# CW308T_STM32FSOCKET_Micro.net
KiCad netlist of a schematic drawn in Altium Designer
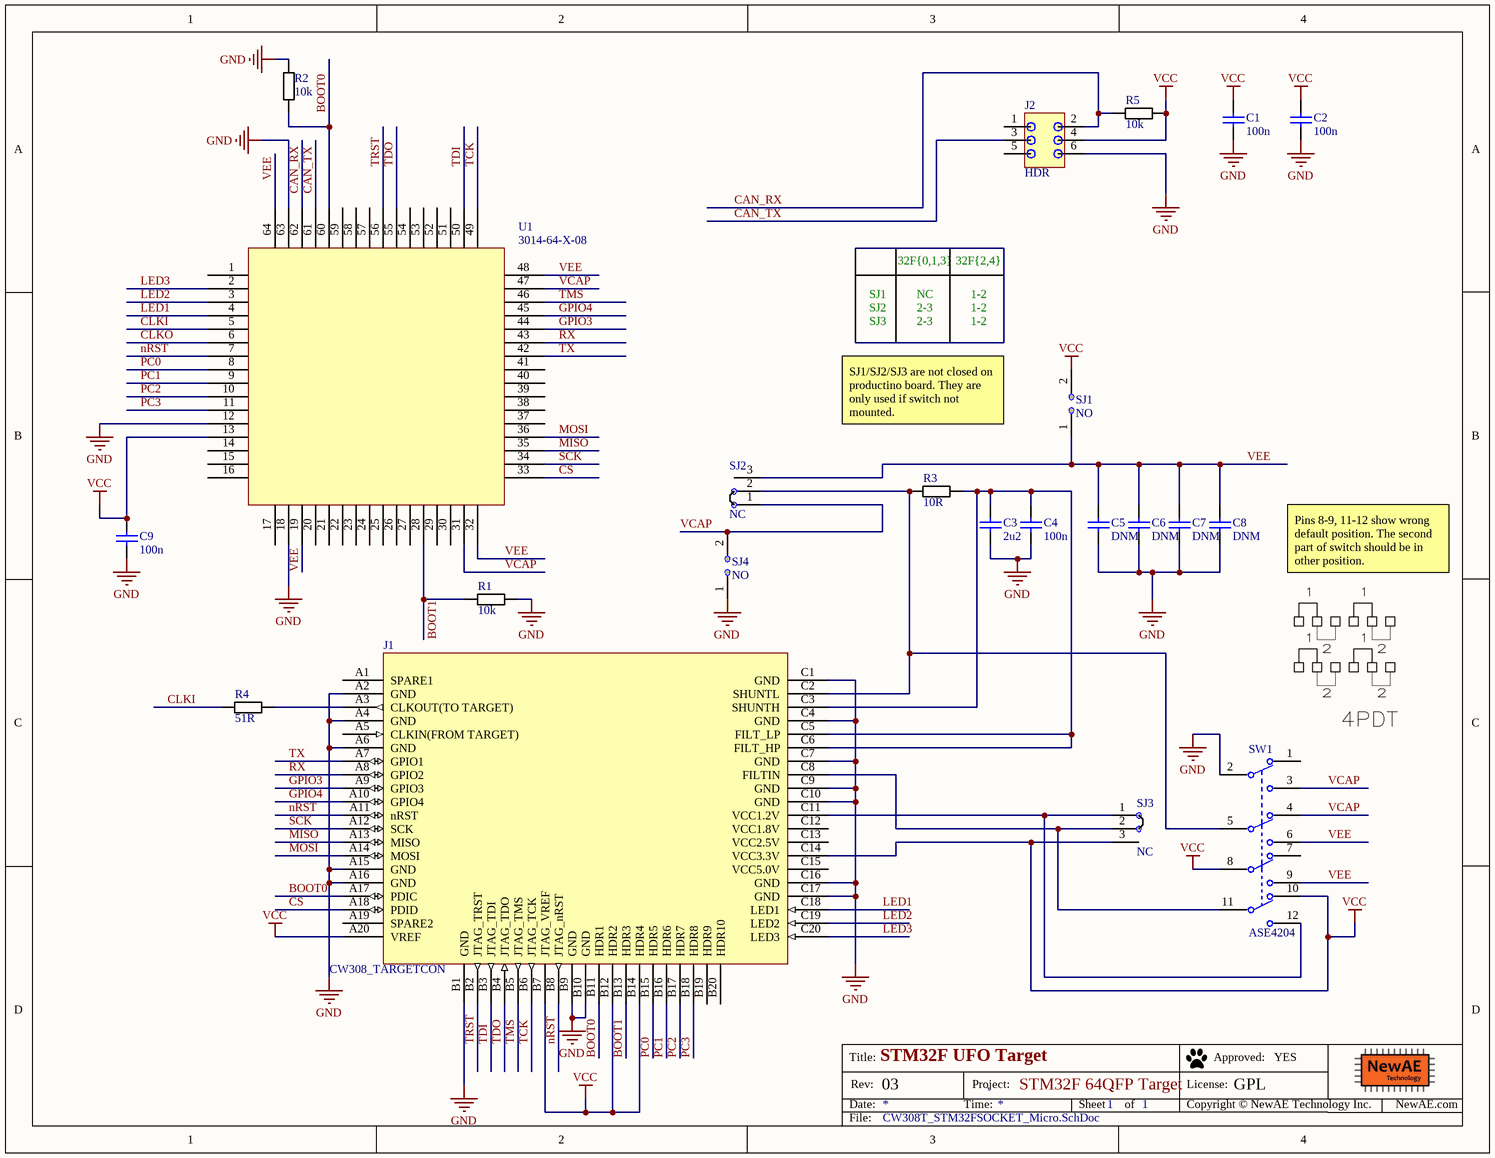
[diagram p0: CW308T_STM32FSOCKET_Micro.SchDoc]

(export (version "E")
  (design (tool "Eeschema 10.0.6"))
  (components
    (comp (ref "C1")
      (value "100n")
      (footprint "CAPC0603_M")
      (description "100n, 0603")
      (fields (field (name "PART NUMBER") "CCHIP-100n-0603"))
      (libsource (lib "NewAE_AltiumLib") (part "CAP"))
    )
    (comp (ref "C2")
      (value "100n")
      (footprint "CAPC0603_M")
      (description "100n, 0603")
      (fields (field (name "PART NUMBER") "CCHIP-100n-0603"))
      (libsource (lib "NewAE_AltiumLib") (part "CAP"))
    )
    (comp (ref "C3")
      (value "2u2")
      (footprint "CAPC0603_M")
      (description "2u2, 0603")
      (fields (field (name "PART NUMBER") "CCHIP-2u2-0603"))
      (libsource (lib "NewAE_AltiumLib") (part "CAP"))
    )
    (comp (ref "C4")
      (value "100n")
      (footprint "CAPC0603_M")
      (description "100n, 0603")
      (fields (field (name "PART NUMBER") "CCHIP-100n-0603"))
      (libsource (lib "NewAE_AltiumLib") (part "CAP"))
    )
    (comp (ref "C5")
      (value "DNM")
      (footprint "CAPC0603_M")
      (description "DNM, 0603")
      (fields (field (name "PART NUMBER") "CCHIP-DNM-0603"))
      (libsource (lib "NewAE_AltiumLib") (part "CAP"))
    )
    (comp (ref "C6")
      (value "DNM")
      (footprint "CAPC0603_M")
      (description "DNM, 0603")
      (fields (field (name "PART NUMBER") "CCHIP-DNM-0603"))
      (libsource (lib "NewAE_AltiumLib") (part "CAP"))
    )
    (comp (ref "C7")
      (value "DNM")
      (footprint "CAPC0603_M")
      (description "DNM, 0603")
      (fields (field (name "PART NUMBER") "CCHIP-DNM-0603"))
      (libsource (lib "NewAE_AltiumLib") (part "CAP"))
    )
    (comp (ref "C8")
      (value "DNM")
      (footprint "CAPC0603_M")
      (description "DNM, 0603")
      (fields (field (name "PART NUMBER") "CCHIP-DNM-0603"))
      (libsource (lib "NewAE_AltiumLib") (part "CAP"))
    )
    (comp (ref "C9")
      (value "100n")
      (footprint "CAPC0603_M")
      (description "100n, 0603")
      (fields (field (name "PART NUMBER") "CCHIP-100n-0603"))
      (libsource (lib "NewAE_AltiumLib") (part "CAP"))
    )
    (comp (ref "J1")
      (value "CW308_TARGETCON")
      (footprint "CW308_TBOARD_CONN")
      (description "CW308 \"Standard\" Target Board Connector")
      (fields (field (name "PART NUMBER") "CW308_TBOARD"))
      (libsource (lib "NewAE_AltiumLib") (part "CW308_TBOARD"))
    )
    (comp (ref "J2")
      (value "HDR")
      (footprint "HDR_6PIN_2ROW_SHROUD")
      (description "HDR, Male, 6-Pin, 2 Row, Shrouded")
      (fields (field (name "PART NUMBER") "HDR_6PIN_2ROW_SHROUD"))
      (libsource (lib "NewAE_AltiumLib") (part "CON6_2ROW"))
    )
    (comp (ref "R1")
      (value "10k")
      (footprint "RESC1608X55N")
      (description "10k res, 0603, 1%, 1/10W")
      (fields (field (name "PART NUMBER") "RCHIP-10K-0603") (field (name "TOLERANCE") "1%"))
      (libsource (lib "NewAE_AltiumLib") (part "RES-EU"))
    )
    (comp (ref "R2")
      (value "10k")
      (footprint "RESC1608X55N")
      (description "10k res, 0603, 1%, 1/10W")
      (fields (field (name "PART NUMBER") "RCHIP-10K-0603") (field (name "TOLERANCE") "1%"))
      (libsource (lib "") (part "RES-EU_1"))
    )
    (comp (ref "R3")
      (value "10R")
      (footprint "RESC1608X55N")
      (description "10R res, 0603, 1%, 1/10W")
      (fields (field (name "PART NUMBER") "RCHIP-10R-0603") (field (name "TOLERANCE") "1%"))
      (libsource (lib "NewAE_AltiumLib") (part "RES-EU"))
    )
    (comp (ref "R4")
      (value "51R")
      (footprint "RESC1608X55N")
      (description "100R res, 0603, 1%, 1/10W")
      (fields (field (name "PART NUMBER") "RCHIP-100R-0603") (field (name "TOLERANCE") "1%"))
      (libsource (lib "NewAE_AltiumLib") (part "RES-EU"))
    )
    (comp (ref "R5")
      (value "10k")
      (footprint "RESC1608X55N")
      (description "10k res, 0603, 1%, 1/10W")
      (fields (field (name "PART NUMBER") "RCHIP-10K-0603") (field (name "TOLERANCE") "1%"))
      (libsource (lib "NewAE_AltiumLib") (part "RES-EU"))
    )
    (comp (ref "SJ1")
      (value "NO")
      (footprint "SJ_2S_NO")
      (description "Solder Jumper, NO")
      (fields (field (name "PART NUMBER") "SJ_2S_NO"))
      (libsource (lib "NewAE_AltiumLib") (part "SJ_2S_NO"))
    )
    (comp (ref "SJ2")
      (value "NC")
      (footprint "SJ_3S_NC12")
      (description "Solder Jumper, NC")
      (fields (field (name "PART NUMBER") "SJ_3S_12JMP"))
      (libsource (lib "NewAE_AltiumLib") (part "SJ_3S_12JMP"))
    )
    (comp (ref "SJ3")
      (value "NC")
      (footprint "SJ_3S_NC12")
      (description "Solder Jumper, NC")
      (fields (field (name "PART NUMBER") "SJ_3S_12JMP"))
      (libsource (lib "NewAE_AltiumLib") (part "SJ_3S_12JMP"))
    )
    (comp (ref "SJ4")
      (value "NO")
      (footprint "SJ_2S_NO")
      (description "Solder Jumper, NO")
      (fields (field (name "PART NUMBER") "SJ_2S_NO"))
      (libsource (lib "NewAE_AltiumLib") (part "SJ_2S_NO"))
    )
    (comp (ref "SW1")
      (value "ASE4204")
      (footprint "FP-ASE4204-MFG")
      (description "Pushbutton Switch SPST-NO Keyswitch, Illuminated Through Hole")
      (libsource (lib "Altium Content Vault") (part "ed2fb4c80255b159646d1d6e4c6c74d"))
    )
    (comp (ref "U1")
      (value "3014-64-X-08")
      (footprint "3014-64-X-08")
      (libsource (lib "tqfp64socket") (part "TQFP64_SOCKET"))
    )
  )
  (nets
    (net (code "1") (name "/BOOT0") (class "Default")
      (node (ref "J1") (pin "A17") (pinfunction "PDIC_A17") (pintype "bidirectional"))
      (node (ref "J1") (pin "B11") (pinfunction "HDR1_B11") (pintype "passive"))
      (node (ref "R2") (pin "1") (pinfunction "1_1") (pintype "passive"))
      (node (ref "U1") (pin "60") (pintype "passive"))
    )
    (net (code "2") (name "/BOOT1") (class "Default")
      (node (ref "J1") (pin "B13") (pinfunction "HDR3_B13") (pintype "passive"))
      (node (ref "R1") (pin "1") (pinfunction "1_1") (pintype "passive"))
      (node (ref "U1") (pin "28") (pintype "passive"))
    )
    (net (code "3") (name "/CAN_RX") (class "Default")
      (node (ref "J2") (pin "2") (pinfunction "2_2") (pintype "passive"))
      (node (ref "R5") (pin "1") (pinfunction "1_1") (pintype "passive"))
      (node (ref "U1") (pin "62") (pintype "passive"))
    )
    (net (code "4") (name "/CAN_TX") (class "Default")
      (node (ref "J2") (pin "3") (pinfunction "3_3") (pintype "passive"))
      (node (ref "U1") (pin "61") (pintype "passive"))
    )
    (net (code "5") (name "/CLKI") (class "Default")
      (node (ref "R4") (pin "1") (pinfunction "1_1") (pintype "passive"))
      (node (ref "U1") (pin "5") (pintype "passive"))
    )
    (net (code "6") (name "/CLKO") (class "Default") (node (ref "U1") (pin "6") (pintype "passive")))
    (net (code "7") (name "/CS") (class "Default")
      (node (ref "J1") (pin "A18") (pinfunction "PDID_A18") (pintype "bidirectional"))
      (node (ref "U1") (pin "33") (pintype "passive"))
    )
    (net (code "8") (name "/GPIO3") (class "Default")
      (node (ref "J1") (pin "A9") (pinfunction "GPIO3_A9") (pintype "bidirectional"))
      (node (ref "U1") (pin "44") (pintype "passive"))
    )
    (net (code "9") (name "/GPIO4") (class "Default")
      (node (ref "J1") (pin "A10") (pinfunction "GPIO4_A10") (pintype "bidirectional"))
      (node (ref "U1") (pin "45") (pintype "passive"))
    )
    (net (code "10") (name "/LED1") (class "Default")
      (node (ref "J1") (pin "C18") (pinfunction "LED1_C18") (pintype "input"))
      (node (ref "U1") (pin "4") (pintype "passive"))
    )
    (net (code "11") (name "/LED2") (class "Default")
      (node (ref "J1") (pin "C19") (pinfunction "LED2_C19") (pintype "input"))
      (node (ref "U1") (pin "3") (pintype "passive"))
    )
    (net (code "12") (name "/LED3") (class "Default")
      (node (ref "J1") (pin "C20") (pinfunction "LED3_C20") (pintype "input"))
      (node (ref "U1") (pin "2") (pintype "passive"))
    )
    (net (code "13") (name "/MISO") (class "Default")
      (node (ref "J1") (pin "A13") (pinfunction "MISO_A13") (pintype "bidirectional"))
      (node (ref "U1") (pin "35") (pintype "passive"))
    )
    (net (code "14") (name "/MOSI") (class "Default")
      (node (ref "J1") (pin "A14") (pinfunction "MOSI_A14") (pintype "bidirectional"))
      (node (ref "U1") (pin "36") (pintype "passive"))
    )
    (net (code "15") (name "/PC0") (class "Default")
      (node (ref "J1") (pin "B15") (pinfunction "HDR5_B15") (pintype "passive"))
      (node (ref "U1") (pin "8") (pintype "passive"))
    )
    (net (code "16") (name "/PC1") (class "Default")
      (node (ref "J1") (pin "B16") (pinfunction "HDR6_B16") (pintype "passive"))
      (node (ref "U1") (pin "9") (pintype "passive"))
    )
    (net (code "17") (name "/PC2") (class "Default")
      (node (ref "J1") (pin "B17") (pinfunction "HDR7_B17") (pintype "passive"))
      (node (ref "U1") (pin "10") (pintype "passive"))
    )
    (net (code "18") (name "/PC3") (class "Default")
      (node (ref "J1") (pin "B18") (pinfunction "HDR8_B18") (pintype "passive"))
      (node (ref "U1") (pin "11") (pintype "passive"))
    )
    (net (code "19") (name "/RX") (class "Default")
      (node (ref "J1") (pin "A8") (pinfunction "GPIO2_A8") (pintype "bidirectional"))
      (node (ref "U1") (pin "43") (pintype "passive"))
    )
    (net (code "20") (name "/SCK") (class "Default")
      (node (ref "J1") (pin "A12") (pinfunction "SCK_A12") (pintype "bidirectional"))
      (node (ref "U1") (pin "34") (pintype "passive"))
    )
    (net (code "21") (name "/TCK") (class "Default")
      (node (ref "J1") (pin "B6") (pinfunction "JTAG_TCK_B6") (pintype "output"))
      (node (ref "U1") (pin "49") (pintype "passive"))
    )
    (net (code "22") (name "/TDI") (class "Default")
      (node (ref "J1") (pin "B3") (pinfunction "JTAG_TDI_B3") (pintype "output"))
      (node (ref "U1") (pin "50") (pintype "passive"))
    )
    (net (code "23") (name "/TDO") (class "Default")
      (node (ref "J1") (pin "B4") (pinfunction "JTAG_TDO_B4") (pintype "input"))
      (node (ref "U1") (pin "55") (pintype "passive"))
    )
    (net (code "24") (name "/TMS") (class "Default")
      (node (ref "J1") (pin "B5") (pinfunction "JTAG_TMS_B5") (pintype "output"))
      (node (ref "U1") (pin "46") (pintype "passive"))
    )
    (net (code "25") (name "/TRST") (class "Default")
      (node (ref "J1") (pin "B2") (pinfunction "JTAG_TRST_B2") (pintype "output"))
      (node (ref "U1") (pin "56") (pintype "passive"))
    )
    (net (code "26") (name "/TX") (class "Default")
      (node (ref "J1") (pin "A7") (pinfunction "GPIO1_A7") (pintype "bidirectional"))
      (node (ref "U1") (pin "42") (pintype "passive"))
    )
    (net (code "27") (name "/VCAP") (class "Default")
      (node (ref "SJ2") (pin "1") (pinfunction "1_1") (pintype "passive"))
      (node (ref "SJ4") (pin "2") (pinfunction "2_2") (pintype "passive"))
      (node (ref "SW1") (pin "3") (pinfunction "3_3") (pintype "passive"))
      (node (ref "SW1") (pin "4") (pinfunction "4_4") (pintype "passive"))
      (node (ref "U1") (pin "31") (pintype "passive"))
      (node (ref "U1") (pin "47") (pintype "passive"))
    )
    (net (code "28") (name "/VEE") (class "Default")
      (node (ref "C5") (pin "1") (pinfunction "1_1") (pintype "passive"))
      (node (ref "C6") (pin "1") (pinfunction "1_1") (pintype "passive"))
      (node (ref "C7") (pin "1") (pinfunction "1_1") (pintype "passive"))
      (node (ref "C8") (pin "1") (pinfunction "1_1") (pintype "passive"))
      (node (ref "SJ1") (pin "1") (pinfunction "1_1") (pintype "passive"))
      (node (ref "SJ2") (pin "3") (pinfunction "3_3") (pintype "passive"))
      (node (ref "SW1") (pin "6") (pinfunction "6_6") (pintype "passive"))
      (node (ref "SW1") (pin "9") (pinfunction "9_9") (pintype "passive"))
      (node (ref "U1") (pin "19") (pintype "passive"))
      (node (ref "U1") (pin "32") (pintype "passive"))
      (node (ref "U1") (pin "48") (pintype "passive"))
      (node (ref "U1") (pin "64") (pintype "passive"))
    )
    (net (code "29") (name "/nRST") (class "Default")
      (node (ref "J1") (pin "A11") (pinfunction "nRST_A11") (pintype "bidirectional"))
      (node (ref "J1") (pin "B8") (pinfunction "JTAG_nRST_B8") (pintype "output"))
      (node (ref "U1") (pin "7") (pintype "passive"))
    )
    (net (code "30") (name "GND") (class "Default")
      (node (ref "C1") (pin "2") (pinfunction "2_2") (pintype "passive"))
      (node (ref "C2") (pin "2") (pinfunction "2_2") (pintype "passive"))
      (node (ref "C3") (pin "2") (pinfunction "2_2") (pintype "passive"))
      (node (ref "C4") (pin "2") (pinfunction "2_2") (pintype "passive"))
      (node (ref "C5") (pin "2") (pinfunction "2_2") (pintype "passive"))
      (node (ref "C6") (pin "2") (pinfunction "2_2") (pintype "passive"))
      (node (ref "C7") (pin "2") (pinfunction "2_2") (pintype "passive"))
      (node (ref "C8") (pin "2") (pinfunction "2_2") (pintype "passive"))
      (node (ref "C9") (pin "2") (pinfunction "2_2") (pintype "passive"))
      (node (ref "J1") (pin "A15") (pinfunction "GND_A15") (pintype "passive"))
      (node (ref "J1") (pin "A16") (pinfunction "GND_A16") (pintype "passive"))
      (node (ref "J1") (pin "A2") (pinfunction "GND_A2") (pintype "passive"))
      (node (ref "J1") (pin "A4") (pinfunction "GND_A4") (pintype "passive"))
      (node (ref "J1") (pin "A6") (pinfunction "GND_A6") (pintype "power_in"))
      (node (ref "J1") (pin "B1") (pinfunction "GND_B1") (pintype "passive"))
      (node (ref "J1") (pin "B10") (pinfunction "GND_B10") (pintype "passive"))
      (node (ref "J1") (pin "B9") (pinfunction "GND_B9") (pintype "passive"))
      (node (ref "J1") (pin "C1") (pinfunction "GND_C1") (pintype "power_in"))
      (node (ref "J1") (pin "C10") (pinfunction "GND_C10") (pintype "power_in"))
      (node (ref "J1") (pin "C16") (pinfunction "GND_C16") (pintype "power_in"))
      (node (ref "J1") (pin "C17") (pinfunction "GND_C17") (pintype "power_in"))
      (node (ref "J1") (pin "C4") (pinfunction "GND_C4") (pintype "power_in"))
      (node (ref "J1") (pin "C7") (pinfunction "GND_C7") (pintype "power_in"))
      (node (ref "J1") (pin "C9") (pinfunction "GND_C9") (pintype "power_in"))
      (node (ref "J2") (pin "6") (pinfunction "6_6") (pintype "passive"))
      (node (ref "R1") (pin "2") (pinfunction "2_2") (pintype "passive"))
      (node (ref "R2") (pin "2") (pinfunction "2_2") (pintype "passive"))
      (node (ref "SJ4") (pin "1") (pinfunction "1_1") (pintype "passive"))
      (node (ref "SW1") (pin "2") (pinfunction "2_2") (pintype "passive"))
      (node (ref "U1") (pin "12") (pintype "passive"))
      (node (ref "U1") (pin "18") (pintype "passive"))
      (node (ref "U1") (pin "63") (pintype "passive"))
    )
    (net (code "31") (name "Net-(J1-CLKOUT(TO_TARGET))") (class "Default")
      (node (ref "J1") (pin "A3") (pinfunction "CLKOUT(TO_TARGET)_A3") (pintype "output"))
      (node (ref "R4") (pin "2") (pinfunction "2_2") (pintype "passive"))
    )
    (net (code "32") (name "Net-(J1-FILTIN)") (class "Default")
      (node (ref "J1") (pin "C8") (pinfunction "FILTIN_C8") (pintype "passive"))
      (node (ref "SJ3") (pin "2") (pinfunction "2_2") (pintype "passive"))
      (node (ref "SW1") (pin "11") (pinfunction "11_11") (pintype "passive"))
    )
    (net (code "33") (name "Net-(J1-FILT_HP)") (class "Default")
      (node (ref "C3") (pin "1") (pinfunction "1_1") (pintype "passive"))
      (node (ref "C4") (pin "1") (pinfunction "1_1") (pintype "passive"))
      (node (ref "J1") (pin "C3") (pinfunction "SHUNTH_C3") (pintype "passive"))
      (node (ref "J1") (pin "C5") (pinfunction "FILT_LP_C5") (pintype "passive"))
      (node (ref "J1") (pin "C6") (pinfunction "FILT_HP_C6") (pintype "passive"))
      (node (ref "R3") (pin "2") (pinfunction "2_2") (pintype "passive"))
    )
    (net (code "34") (name "Net-(J1-SHUNTL)") (class "Default")
      (node (ref "J1") (pin "C2") (pinfunction "SHUNTL_C2") (pintype "passive"))
      (node (ref "R3") (pin "1") (pinfunction "1_1") (pintype "passive"))
      (node (ref "SJ2") (pin "2") (pinfunction "2_2") (pintype "passive"))
      (node (ref "SW1") (pin "5") (pinfunction "5_5") (pintype "passive"))
    )
    (net (code "35") (name "Net-(J1-VCC1.2V)") (class "Default")
      (node (ref "J1") (pin "C11") (pinfunction "VCC1.2V_C11") (pintype "power_in"))
      (node (ref "SJ3") (pin "1") (pinfunction "1_1") (pintype "passive"))
      (node (ref "SW1") (pin "12") (pinfunction "12_12") (pintype "passive"))
    )
    (net (code "36") (name "VCC") (class "Default")
      (node (ref "C1") (pin "1") (pinfunction "1_1") (pintype "passive"))
      (node (ref "C2") (pin "1") (pinfunction "1_1") (pintype "passive"))
      (node (ref "C9") (pin "1") (pinfunction "1_1") (pintype "passive"))
      (node (ref "J1") (pin "A20") (pinfunction "VREF_A20") (pintype "tri_state"))
      (node (ref "J1") (pin "B12") (pinfunction "HDR2_B12") (pintype "passive"))
      (node (ref "J1") (pin "B14") (pinfunction "HDR4_B14") (pintype "passive"))
      (node (ref "J1") (pin "B7") (pinfunction "JTAG_VREF_B7") (pintype "tri_state"))
      (node (ref "J1") (pin "C14") (pinfunction "VCC3.3V_C14") (pintype "power_in"))
      (node (ref "J2") (pin "4") (pinfunction "4_4") (pintype "passive"))
      (node (ref "R5") (pin "2") (pinfunction "2_2") (pintype "passive"))
      (node (ref "SJ1") (pin "2") (pinfunction "2_2") (pintype "passive"))
      (node (ref "SJ3") (pin "3") (pinfunction "3_3") (pintype "passive"))
      (node (ref "SW1") (pin "10") (pinfunction "10_10") (pintype "passive"))
      (node (ref "SW1") (pin "8") (pinfunction "8_8") (pintype "passive"))
      (node (ref "U1") (pin "13") (pintype "passive"))
    )
    (net (code "37") (name "unconnected-(J1-CLKIN(FROM_TARGET)-PadA5)") (class "Default")
      (node (ref "J1") (pin "A5") (pinfunction "CLKIN(FROM_TARGET)_A5") (pintype "input"))
    )
    (net (code "38") (name "unconnected-(J1-HDR9-PadB19)") (class "Default")
      (node (ref "J1") (pin "B19") (pinfunction "HDR9_B19") (pintype "passive"))
    )
    (net (code "39") (name "unconnected-(J1-HDR10-PadB20)") (class "Default")
      (node (ref "J1") (pin "B20") (pinfunction "HDR10_B20") (pintype "passive"))
    )
    (net (code "40") (name "unconnected-(J1-SPARE1-PadA1)") (class "Default")
      (node (ref "J1") (pin "A1") (pinfunction "SPARE1_A1") (pintype "passive"))
    )
    (net (code "41") (name "unconnected-(J1-SPARE2-PadA19)") (class "Default")
      (node (ref "J1") (pin "A19") (pinfunction "SPARE2_A19") (pintype "passive"))
    )
    (net (code "42") (name "unconnected-(J1-VCC1.8V-PadC12)") (class "Default")
      (node (ref "J1") (pin "C12") (pinfunction "VCC1.8V_C12") (pintype "power_in"))
    )
    (net (code "43") (name "unconnected-(J1-VCC2.5V-PadC13)") (class "Default")
      (node (ref "J1") (pin "C13") (pinfunction "VCC2.5V_C13") (pintype "power_in"))
    )
    (net (code "44") (name "unconnected-(J1-VCC5.0V-PadC15)") (class "Default")
      (node (ref "J1") (pin "C15") (pinfunction "VCC5.0V_C15") (pintype "power_in"))
    )
    (net (code "45") (name "unconnected-(J2-Pad1)") (class "Default")
      (node (ref "J2") (pin "1") (pinfunction "1_1") (pintype "passive"))
    )
    (net (code "46") (name "unconnected-(J2-Pad5)") (class "Default")
      (node (ref "J2") (pin "5") (pinfunction "5_5") (pintype "passive"))
    )
    (net (code "47") (name "unconnected-(SW1-Pad1)") (class "Default")
      (node (ref "SW1") (pin "1") (pinfunction "1_1") (pintype "passive"))
    )
    (net (code "48") (name "unconnected-(SW1-Pad7)") (class "Default")
      (node (ref "SW1") (pin "7") (pinfunction "7_7") (pintype "passive"))
    )
    (net (code "49") (name "unconnected-(U1-Pad1)") (class "Default")
      (node (ref "U1") (pin "1") (pintype "passive"))
    )
    (net (code "50") (name "unconnected-(U1-Pad14)") (class "Default")
      (node (ref "U1") (pin "14") (pintype "passive"))
    )
    (net (code "51") (name "unconnected-(U1-Pad15)") (class "Default")
      (node (ref "U1") (pin "15") (pintype "passive"))
    )
    (net (code "52") (name "unconnected-(U1-Pad16)") (class "Default")
      (node (ref "U1") (pin "16") (pintype "passive"))
    )
    (net (code "53") (name "unconnected-(U1-Pad17)") (class "Default")
      (node (ref "U1") (pin "17") (pintype "passive"))
    )
    (net (code "54") (name "unconnected-(U1-Pad20)") (class "Default")
      (node (ref "U1") (pin "20") (pintype "passive"))
    )
    (net (code "55") (name "unconnected-(U1-Pad21)") (class "Default")
      (node (ref "U1") (pin "21") (pintype "passive"))
    )
    (net (code "56") (name "unconnected-(U1-Pad22)") (class "Default")
      (node (ref "U1") (pin "22") (pintype "passive"))
    )
    (net (code "57") (name "unconnected-(U1-Pad23)") (class "Default")
      (node (ref "U1") (pin "23") (pintype "passive"))
    )
    (net (code "58") (name "unconnected-(U1-Pad24)") (class "Default")
      (node (ref "U1") (pin "24") (pintype "passive"))
    )
    (net (code "59") (name "unconnected-(U1-Pad25)") (class "Default")
      (node (ref "U1") (pin "25") (pintype "passive"))
    )
    (net (code "60") (name "unconnected-(U1-Pad26)") (class "Default")
      (node (ref "U1") (pin "26") (pintype "passive"))
    )
    (net (code "61") (name "unconnected-(U1-Pad27)") (class "Default")
      (node (ref "U1") (pin "27") (pintype "passive"))
    )
    (net (code "62") (name "unconnected-(U1-Pad29)") (class "Default")
      (node (ref "U1") (pin "29") (pintype "passive"))
    )
    (net (code "63") (name "unconnected-(U1-Pad30)") (class "Default")
      (node (ref "U1") (pin "30") (pintype "passive"))
    )
    (net (code "64") (name "unconnected-(U1-Pad37)") (class "Default")
      (node (ref "U1") (pin "37") (pintype "passive"))
    )
    (net (code "65") (name "unconnected-(U1-Pad38)") (class "Default")
      (node (ref "U1") (pin "38") (pintype "passive"))
    )
    (net (code "66") (name "unconnected-(U1-Pad39)") (class "Default")
      (node (ref "U1") (pin "39") (pintype "passive"))
    )
    (net (code "67") (name "unconnected-(U1-Pad40)") (class "Default")
      (node (ref "U1") (pin "40") (pintype "passive"))
    )
    (net (code "68") (name "unconnected-(U1-Pad41)") (class "Default")
      (node (ref "U1") (pin "41") (pintype "passive"))
    )
    (net (code "69") (name "unconnected-(U1-Pad51)") (class "Default")
      (node (ref "U1") (pin "51") (pintype "passive"))
    )
    (net (code "70") (name "unconnected-(U1-Pad52)") (class "Default")
      (node (ref "U1") (pin "52") (pintype "passive"))
    )
    (net (code "71") (name "unconnected-(U1-Pad53)") (class "Default")
      (node (ref "U1") (pin "53") (pintype "passive"))
    )
    (net (code "72") (name "unconnected-(U1-Pad54)") (class "Default")
      (node (ref "U1") (pin "54") (pintype "passive"))
    )
    (net (code "73") (name "unconnected-(U1-Pad57)") (class "Default")
      (node (ref "U1") (pin "57") (pintype "passive"))
    )
    (net (code "74") (name "unconnected-(U1-Pad58)") (class "Default")
      (node (ref "U1") (pin "58") (pintype "passive"))
    )
    (net (code "75") (name "unconnected-(U1-Pad59)") (class "Default")
      (node (ref "U1") (pin "59") (pintype "passive"))
    )
  )
)
